# untitled.net
KiCad netlist of a schematic drawn in EAGLE
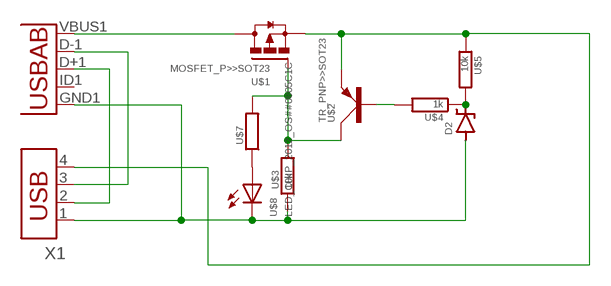
[diagram p0: schematic, sheet 1]

(export (version "E")
  (design (tool "Eeschema 10.0.6"))
  (components
    (comp (ref "D2")
      (value "ZENER-DIODE>>SOD-323")
      (footprint "eagle-import:SOD323-W")
      (libsource (lib "eagle-import") (part "ZENER-DIODE{gt}{gt}SOD-323"))
    )
    (comp (ref "U$1")
      (value "MOSFET_P>>SOT23")
      (footprint "eagle-import:SOT23")
      (libsource (lib "eagle-import") (part "MOSFET_P{gt}{gt}SOT23"))
    )
    (comp (ref "U$2")
      (value "TR_PNP>>SOT23")
      (footprint "eagle-import:SOT23")
      (libsource (lib "eagle-import") (part "TR_PNP{gt}{gt}SOT23"))
    )
    (comp (ref "U$3")
      (value "10k")
      (footprint "eagle-import:2012")
      (libsource (lib "eagle-import") (part "REGISTER{gt}{gt}2012"))
    )
    (comp (ref "U$4")
      (value "1k")
      (footprint "eagle-import:2012")
      (libsource (lib "eagle-import") (part "REGISTER{gt}{gt}2012"))
    )
    (comp (ref "U$5")
      (value "10k")
      (footprint "eagle-import:2012")
      (libsource (lib "eagle-import") (part "REGISTER{gt}{gt}2012"))
    )
    (comp (ref "U$7")
      (value "REGISTER>>2012")
      (footprint "eagle-import:2012")
      (libsource (lib "eagle-import") (part "REGISTER{gt}{gt}2012"))
    )
    (comp (ref "U$8")
      (value "LED_CHIP_2012_OS##0805C1C")
      (footprint "eagle-import:2012_OS##0805C1C")
      (libsource (lib "eagle-import") (part "LED_CHIP_2012_OS##0805C1C"))
    )
    (comp (ref "U1")
      (value "USB\"\"")
      (footprint "eagle-import:USB-MICRO-SMD")
      (libsource (lib "eagle-import") (part "USB{dblquote}{dblquote}"))
    )
    (comp (ref "X1")
      (value "USB-787616")
      (footprint "eagle-import:USB")
      (libsource (lib "eagle-import") (part "USB-787616"))
    )
  )
  (nets
    (net (code "1") (name "Net-(D2-PadC)") (class "Default")
      (node (ref "D2") (pin "C") (pinfunction "C_C") (pintype "passive"))
      (node (ref "U$4") (pin "1") (pinfunction "1_1") (pintype "passive"))
      (node (ref "U$5") (pin "2") (pinfunction "2_2") (pintype "passive"))
    )
    (net (code "2") (name "Net-(U$1-D)") (class "Default")
      (node (ref "U$1") (pin "3") (pinfunction "D_3") (pintype "passive"))
      (node (ref "U1") (pin "VBUS1") (pinfunction "VBUS_VBUS1") (pintype "bidirectional"))
    )
    (net (code "3") (name "Net-(U$1-G)") (class "Default")
      (node (ref "U$1") (pin "1") (pinfunction "G_1") (pintype "passive"))
      (node (ref "U$2") (pin "3") (pinfunction "C_3") (pintype "passive"))
      (node (ref "U$3") (pin "2") (pinfunction "2_2") (pintype "passive"))
      (node (ref "U$7") (pin "2") (pinfunction "2_2") (pintype "passive"))
    )
    (net (code "4") (name "Net-(U$1-S)") (class "Default")
      (node (ref "U$1") (pin "2") (pinfunction "S_2") (pintype "passive"))
      (node (ref "U$2") (pin "2") (pinfunction "E_2") (pintype "passive"))
      (node (ref "U$5") (pin "1") (pinfunction "1_1") (pintype "passive"))
      (node (ref "X1") (pin "4") (pinfunction "4_4") (pintype "passive"))
    )
    (net (code "5") (name "Net-(U$2-B)") (class "Default")
      (node (ref "U$2") (pin "1") (pinfunction "B_1") (pintype "passive"))
      (node (ref "U$4") (pin "2") (pinfunction "2_2") (pintype "passive"))
    )
    (net (code "6") (name "Net-(U$8-A)") (class "Default")
      (node (ref "U$7") (pin "1") (pinfunction "1_1") (pintype "passive"))
      (node (ref "U$8") (pin "P$1") (pinfunction "A_P$1") (pintype "passive"))
    )
    (net (code "7") (name "Net-(U$8-C)") (class "Default")
      (node (ref "D2") (pin "A") (pinfunction "A_A") (pintype "passive"))
      (node (ref "U$3") (pin "1") (pinfunction "1_1") (pintype "passive"))
      (node (ref "U$8") (pin "P$2") (pinfunction "C_P$2") (pintype "passive"))
      (node (ref "U1") (pin "GND1") (pinfunction "GND_GND1") (pintype "bidirectional"))
      (node (ref "X1") (pin "1") (pinfunction "1_1") (pintype "passive"))
    )
    (net (code "8") (name "Net-(U1-D+)") (class "Default")
      (node (ref "U1") (pin "D+1") (pinfunction "D+_D+1") (pintype "bidirectional"))
      (node (ref "X1") (pin "2") (pinfunction "2_2") (pintype "passive"))
    )
    (net (code "9") (name "Net-(U1-D-)") (class "Default")
      (node (ref "U1") (pin "D-1") (pinfunction "D-_D-1") (pintype "bidirectional"))
      (node (ref "X1") (pin "3") (pinfunction "3_3") (pintype "passive"))
    )
    (net (code "10") (name "unconnected-(U1-USBID-PadID1)") (class "Default")
      (node (ref "U1") (pin "ID1") (pinfunction "USBID_ID1") (pintype "bidirectional"))
    )
  )
)
